# 3-VW_MODULE.net
KiCad netlist of a schematic drawn in Altium Designer
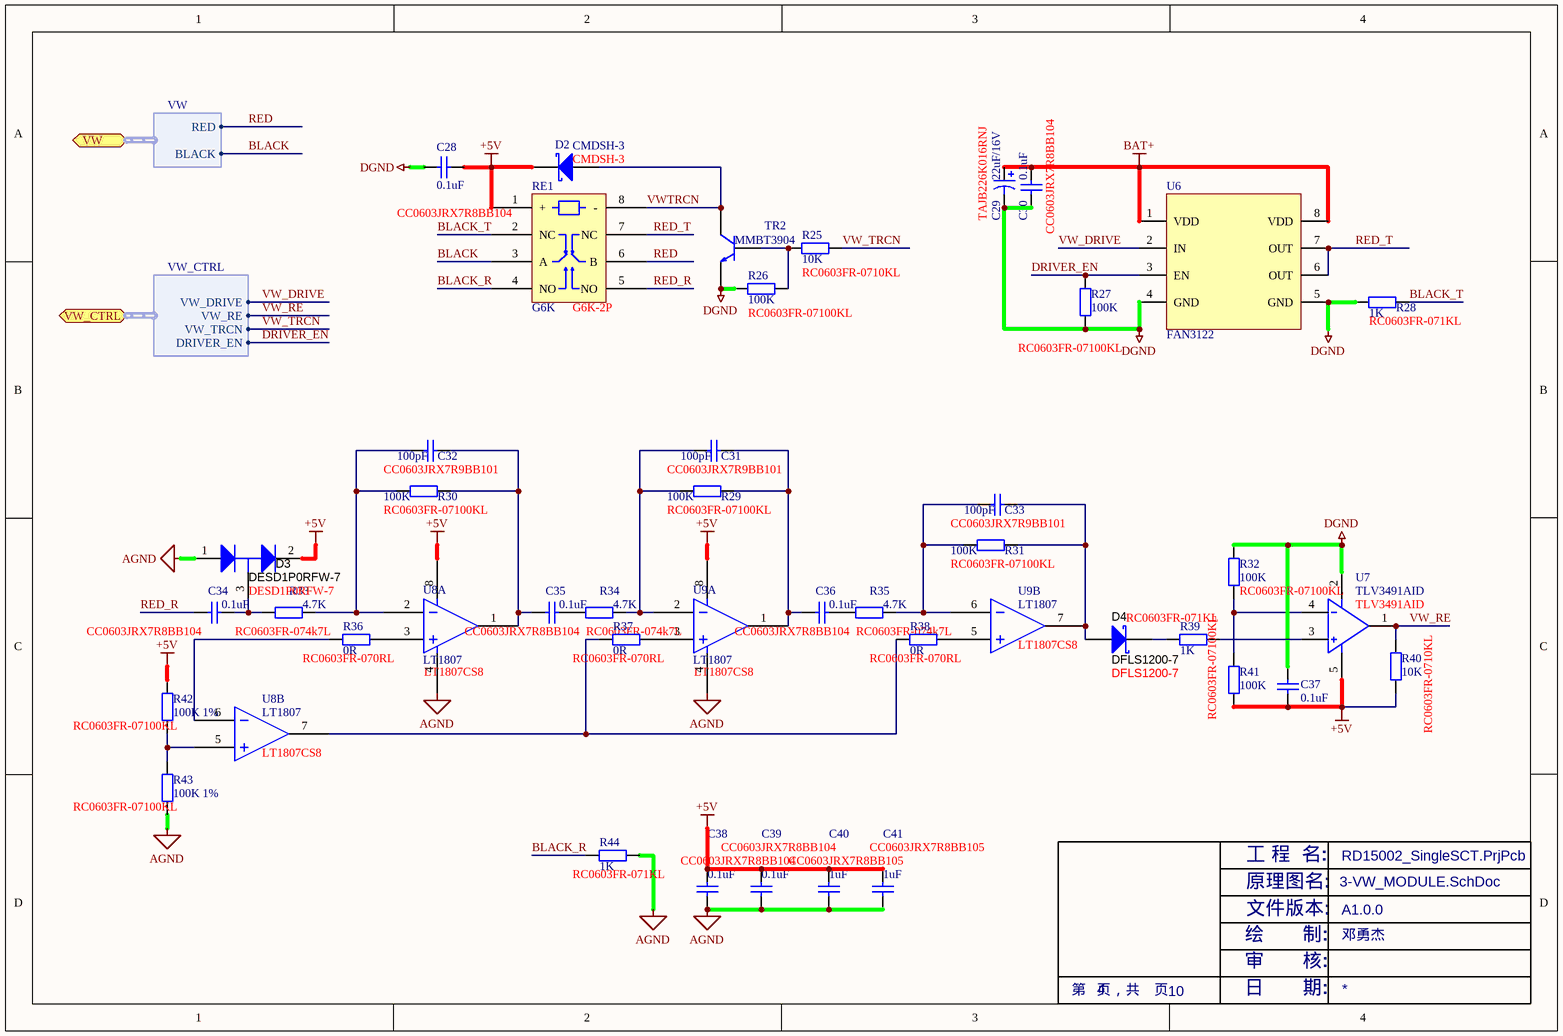
[diagram p0: 3-VW_MODULE.SchDoc]

(export (version "E")
  (design (tool "Eeschema 10.0.6"))
  (components
    (comp (ref "C28")
      (value "0.1uF")
      (footprint "CC0603")
      (description "Capacitor")
      (fields (field (name "TYPE NO.") "CC0603JRX7R8BB104"))
      (libsource (lib "Miscellaneous Devices") (part "Cap"))
    )
    (comp (ref "C29")
      (value "22uF/16V")
      (footprint "CB3528")
      (description "Polarized Capacitor (Radial)")
      (fields (field (name "PART NO.") "TAJB226K016RNJ"))
      (libsource (lib "Miscellaneous Devices") (part "Cap Pol1"))
    )
    (comp (ref "C30")
      (value "0.1uF")
      (footprint "CC0603")
      (description "Capacitor")
      (fields (field (name "TYPE NO.") "CC0603JRX7R8BB104"))
      (libsource (lib "Miscellaneous Devices") (part "Cap"))
    )
    (comp (ref "C31")
      (value "100pF")
      (footprint "CC0603")
      (description "Capacitor")
      (fields (field (name "TYPE NO.") "CC0603JRX7R9BB101"))
      (libsource (lib "Miscellaneous Devices") (part "Cap"))
    )
    (comp (ref "C32")
      (value "100pF")
      (footprint "CC0603")
      (description "Capacitor")
      (fields (field (name "TYPE NO.") "CC0603JRX7R9BB101"))
      (libsource (lib "Miscellaneous Devices") (part "Cap"))
    )
    (comp (ref "C33")
      (value "100pF")
      (footprint "CC0603")
      (description "Capacitor")
      (fields (field (name "TYPE NO.") "CC0603JRX7R9BB101"))
      (libsource (lib "Miscellaneous Devices") (part "Cap"))
    )
    (comp (ref "C34")
      (value "0.1uF")
      (footprint "CC0603")
      (description "Capacitor")
      (fields (field (name "TYPE NO.") "CC0603JRX7R8BB104"))
      (libsource (lib "Miscellaneous Devices") (part "Cap"))
    )
    (comp (ref "C35")
      (value "0.1uF")
      (footprint "CC0603")
      (description "Capacitor")
      (fields (field (name "TYPE NO.") "CC0603JRX7R8BB104"))
      (libsource (lib "Miscellaneous Devices") (part "Cap"))
    )
    (comp (ref "C36")
      (value "0.1uF")
      (footprint "CC0603")
      (description "Capacitor")
      (fields (field (name "TYPE NO.") "CC0603JRX7R8BB104"))
      (libsource (lib "Miscellaneous Devices") (part "Cap"))
    )
    (comp (ref "C37")
      (value "0.1uF")
      (footprint "CC0603")
      (description "Capacitor")
      (fields (field (name "PUBLISHER") "Altium Limited"))
      (libsource (lib "Miscellaneous Devices") (part "Cap"))
    )
    (comp (ref "C38")
      (value "0.1uF")
      (footprint "CC0603")
      (description "Capacitor")
      (fields (field (name "TYPE NO.") "CC0603JRX7R8BB104"))
      (libsource (lib "Miscellaneous Devices") (part "Cap"))
    )
    (comp (ref "C39")
      (value "0.1uF")
      (footprint "CC0603")
      (description "Capacitor")
      (fields (field (name "TYPE NO.") "CC0603JRX7R8BB104"))
      (libsource (lib "Miscellaneous Devices") (part "Cap"))
    )
    (comp (ref "C40")
      (value "1uF")
      (footprint "CC0603")
      (description "Capacitor")
      (fields (field (name "TYPE NO.") "CC0603JRX7R8BB105"))
      (libsource (lib "Miscellaneous Devices") (part "Cap"))
    )
    (comp (ref "C41")
      (value "1uF")
      (footprint "CC0603")
      (description "Capacitor")
      (fields (field (name "TYPE NO.") "CC0603JRX7R8BB105"))
      (libsource (lib "Miscellaneous Devices") (part "Cap"))
    )
    (comp (ref "D2")
      (value "CMDSH-3")
      (footprint "SOD323")
      (description "Schottky Diode")
      (fields (field (name "TYPE NO.") "CMDSH-3"))
      (libsource (lib "Miscellaneous Devices") (part "D Schottky"))
    )
    (comp (ref "D3")
      (value "DESD1P0RFW-7")
      (footprint "SOT-323")
      (description "TVS DIODE,70VVVM,8VC,SOT-323")
      (fields (field (name "TYPE NO.") "DESD1P0RFW-7"))
      (libsource (lib "Diode") (part "BAV99WT1G"))
    )
    (comp (ref "D4")
      (value "DFLS1200-7")
      (footprint "powerDI123")
      (description "Diode, Schotky, 200V, 1A, PowerDI123")
      (fields (field (name "PART NO.") "DFLS1200-7"))
      (libsource (lib "Diode") (part "DFLS1200-7"))
    )
    (comp (ref "R25")
      (value "10K")
      (footprint "CC0603")
      (description "Resistor")
      (fields (field (name "TYPE NO.") "RC0603FR-0710KL"))
      (libsource (lib "") (part "Res2_1"))
    )
    (comp (ref "R26")
      (value "100K")
      (footprint "CC0603")
      (description "Resistor")
      (fields (field (name "TYPE NO.") "RC0603FR-07100KL"))
      (libsource (lib "") (part "Res2_1"))
    )
    (comp (ref "R27")
      (value "100K")
      (footprint "CC0603")
      (description "Resistor")
      (fields (field (name "TYPE NO.") "RC0603FR-07100KL"))
      (libsource (lib "") (part "Res2_2"))
    )
    (comp (ref "R28")
      (value "1K")
      (footprint "CC0603")
      (description "Resistor")
      (fields (field (name "TYPE NO.") "RC0603FR-071KL"))
      (libsource (lib "Miscellaneous Devices") (part "Res2"))
    )
    (comp (ref "R29")
      (value "100K")
      (footprint "CC0603")
      (description "Resistor")
      (fields (field (name "TYPE NO.") "RC0603FR-07100KL"))
      (libsource (lib "Miscellaneous Devices") (part "Res2"))
    )
    (comp (ref "R30")
      (value "100K")
      (footprint "CC0603")
      (description "Resistor")
      (fields (field (name "TYPE NO.") "RC0603FR-07100KL"))
      (libsource (lib "Miscellaneous Devices") (part "Res2"))
    )
    (comp (ref "R31")
      (value "100K")
      (footprint "CC0603")
      (description "Resistor")
      (fields (field (name "TYPE NO.") "RC0603FR-07100KL"))
      (libsource (lib "Miscellaneous Devices") (part "Res2"))
    )
    (comp (ref "R32")
      (value "100K")
      (footprint "CC0603")
      (description "Resistor")
      (fields (field (name "TYPE NO.") "RC0603FR-07100KL"))
      (libsource (lib "") (part "Res2_1"))
    )
    (comp (ref "R33")
      (value "4.7K")
      (footprint "CC0603")
      (description "Resistor")
      (fields (field (name "TYPE NO.") "RC0603FR-074k7L"))
      (libsource (lib "Miscellaneous Devices") (part "Res2"))
    )
    (comp (ref "R34")
      (value "4.7K")
      (footprint "CC0603")
      (description "Resistor")
      (fields (field (name "TYPE NO.") "RC0603FR-074k7L"))
      (libsource (lib "Miscellaneous Devices") (part "Res2"))
    )
    (comp (ref "R35")
      (value "4.7K")
      (footprint "CC0603")
      (description "Resistor")
      (fields (field (name "TYPE NO.") "RC0603FR-074k7L"))
      (libsource (lib "Miscellaneous Devices") (part "Res2"))
    )
    (comp (ref "R36")
      (value "0R")
      (footprint "CC0603")
      (description "Resistor")
      (fields (field (name "TYPE NO.") "RC0603FR-070RL"))
      (libsource (lib "Miscellaneous Devices") (part "Res2"))
    )
    (comp (ref "R37")
      (value "0R")
      (footprint "CC0603")
      (description "Resistor")
      (fields (field (name "TYPE NO.") "RC0603FR-070RL"))
      (libsource (lib "Miscellaneous Devices") (part "Res2"))
    )
    (comp (ref "R38")
      (value "0R")
      (footprint "CC0603")
      (description "Resistor")
      (fields (field (name "TYPE NO.") "RC0603FR-070RL"))
      (libsource (lib "Miscellaneous Devices") (part "Res2"))
    )
    (comp (ref "R39")
      (value "1K")
      (footprint "CC0603")
      (description "Resistor")
      (fields (field (name "TYPE NO.") "RC0603FR-071KL"))
      (libsource (lib "Miscellaneous Devices") (part "Res2"))
    )
    (comp (ref "R40")
      (value "10K")
      (footprint "CC0603")
      (description "Resistor")
      (fields (field (name "TYPE NO.") "RC0603FR-0710KL"))
      (libsource (lib "") (part "Res2_1"))
    )
    (comp (ref "R41")
      (value "100K")
      (footprint "CC0603")
      (description "Resistor")
      (fields (field (name "TYPE NO.") "RC0603FR-07100KL"))
      (libsource (lib "") (part "Res2_1"))
    )
    (comp (ref "R42")
      (value "100K 1%")
      (footprint "CC0603")
      (description "Resistor")
      (fields (field (name "TYPE NO.") "RC0603FR-07100KL"))
      (libsource (lib "") (part "Res2_2"))
    )
    (comp (ref "R43")
      (value "100K 1%")
      (footprint "CC0603")
      (description "Resistor")
      (fields (field (name "TYPE NO.") "RC0603FR-07100KL"))
      (libsource (lib "") (part "Res2_2"))
    )
    (comp (ref "R44")
      (value "1K")
      (footprint "CC0603")
      (description "Resistor")
      (fields (field (name "TYPE NO.") "RC0603FR-071KL"))
      (libsource (lib "") (part "Res2_3"))
    )
    (comp (ref "RE1")
      (value "G6K")
      (footprint "G6K")
      (fields (field (name "TYPE NO.") "G6K-2P"))
      (libsource (lib "woylib2015") (part "G6K"))
    )
    (comp (ref "TR2") (value "MMBT3904") (footprint "SOT-23W") (libsource (lib "Discrete") (part "NPN")))
    (comp (ref "U6") (value "FAN3122") (footprint "SO-8") (libsource (lib "IC") (part "FAN3122")))
    (comp (ref "U7")
      (value "TLV3491AID")
      (footprint "SOT-23-5")
      (fields (field (name "TYPE NO.") "TLV3491AID"))
      (libsource (lib "woylib2015") (part "TLV3491AID"))
    )
    (comp (ref "U8")
      (value "LT1807")
      (footprint "SO-8")
      (fields (field (name "TYPE NO.") "LT1807CS8"))
      (libsource (lib "woylib2015") (part "LM833N"))
    )
    (comp (ref "U9")
      (value "LT1807")
      (footprint "SO-8")
      (fields (field (name "TYPE NO.") "LT1807CS8"))
      (libsource (lib "woylib2015") (part "LM833N"))
    )
  )
  (nets
    (net (code "3") (name "+5V") (class "Default")
      (node (ref "C28") (pin "1") (pinfunction "1_1") (pintype "passive"))
      (node (ref "C37") (pin "2") (pinfunction "2_2") (pintype "passive"))
      (node (ref "C38") (pin "2") (pinfunction "2_2") (pintype "passive"))
      (node (ref "C39") (pin "2") (pinfunction "2_2") (pintype "passive"))
      (node (ref "C40") (pin "2") (pinfunction "2_2") (pintype "passive"))
      (node (ref "C41") (pin "2") (pinfunction "2_2") (pintype "passive"))
      (node (ref "D2") (pin "2") (pinfunction "K_2") (pintype "passive"))
      (node (ref "D3") (pin "2") (pinfunction "K_2") (pintype "passive"))
      (node (ref "R40") (pin "1") (pinfunction "1_1") (pintype "passive"))
      (node (ref "R41") (pin "1") (pinfunction "1_1") (pintype "passive"))
      (node (ref "R42") (pin "1") (pinfunction "1_1") (pintype "passive"))
      (node (ref "RE1") (pin "1") (pinfunction "+_1") (pintype "passive"))
      (node (ref "U7") (pin "5") (pinfunction "+VS_5") (pintype "passive"))
      (node (ref "U8") (pin "8") (pintype "passive"))
      (node (ref "U9") (pin "8") (pintype "passive"))
    )
    (net (code "4") (name "/BLACK") (class "Default")
      (node (ref "RE1") (pin "3") (pinfunction "A_3") (pintype "passive"))
    )
    (net (code "5") (name "/BLACK_R") (class "Default")
      (node (ref "R44") (pin "1") (pinfunction "1_1") (pintype "passive"))
      (node (ref "RE1") (pin "4") (pinfunction "NO_4") (pintype "passive"))
    )
    (net (code "6") (name "/BLACK_T") (class "Default")
      (node (ref "R28") (pin "1") (pinfunction "1_1") (pintype "passive"))
      (node (ref "RE1") (pin "2") (pinfunction "NC_2") (pintype "passive"))
    )
    (net (code "7") (name "/DRIVER_EN") (class "Default")
      (node (ref "R27") (pin "1") (pinfunction "1_1") (pintype "passive"))
      (node (ref "U6") (pin "3") (pinfunction "EN_3") (pintype "passive"))
    )
    (net (code "8") (name "/RED") (class "Default")
      (node (ref "RE1") (pin "6") (pinfunction "B_6") (pintype "passive"))
    )
    (net (code "9") (name "/RED_R") (class "Default")
      (node (ref "C34") (pin "2") (pinfunction "2_2") (pintype "passive"))
      (node (ref "RE1") (pin "5") (pinfunction "NO_5") (pintype "passive"))
    )
    (net (code "10") (name "/RED_T") (class "Default")
      (node (ref "RE1") (pin "7") (pinfunction "NC_7") (pintype "passive"))
      (node (ref "U6") (pin "6") (pinfunction "OUT_6") (pintype "passive"))
      (node (ref "U6") (pin "7") (pinfunction "OUT_7") (pintype "passive"))
    )
    (net (code "11") (name "/VWTRCN") (class "Default")
      (node (ref "D2") (pin "1") (pinfunction "A_1") (pintype "passive"))
      (node (ref "RE1") (pin "8") (pinfunction "-_8") (pintype "passive"))
      (node (ref "TR2") (pin "3") (pinfunction "3_3") (pintype "passive"))
    )
    (net (code "12") (name "/VW_DRIVE") (class "Default")
      (node (ref "U6") (pin "2") (pinfunction "IN_2") (pintype "passive"))
    )
    (net (code "13") (name "/VW_RE") (class "Default")
      (node (ref "R40") (pin "2") (pinfunction "2_2") (pintype "passive"))
      (node (ref "U7") (pin "1") (pinfunction "OUT_1") (pintype "passive"))
    )
    (net (code "14") (name "/VW_TRCN") (class "Default")
      (node (ref "R25") (pin "2") (pinfunction "2_2") (pintype "passive"))
    )
    (net (code "17") (name "AGND") (class "Default")
      (node (ref "C38") (pin "1") (pinfunction "1_1") (pintype "passive"))
      (node (ref "C39") (pin "1") (pinfunction "1_1") (pintype "passive"))
      (node (ref "C40") (pin "1") (pinfunction "1_1") (pintype "passive"))
      (node (ref "C41") (pin "1") (pinfunction "1_1") (pintype "passive"))
      (node (ref "D3") (pin "1") (pinfunction "A_1") (pintype "passive"))
      (node (ref "R43") (pin "2") (pinfunction "2_2") (pintype "passive"))
      (node (ref "R44") (pin "2") (pinfunction "2_2") (pintype "passive"))
      (node (ref "U8") (pin "4") (pintype "passive"))
      (node (ref "U9") (pin "4") (pintype "passive"))
    )
    (net (code "18") (name "BAT+") (class "Default")
      (node (ref "C29") (pin "1") (pinfunction "1_1") (pintype "passive"))
      (node (ref "C30") (pin "2") (pinfunction "2_2") (pintype "passive"))
      (node (ref "U6") (pin "1") (pinfunction "VDD_1") (pintype "passive"))
      (node (ref "U6") (pin "8") (pinfunction "VDD_8") (pintype "passive"))
    )
    (net (code "19") (name "DGND") (class "Default")
      (node (ref "C28") (pin "2") (pinfunction "2_2") (pintype "passive"))
      (node (ref "C29") (pin "2") (pinfunction "2_2") (pintype "passive"))
      (node (ref "C30") (pin "1") (pinfunction "1_1") (pintype "passive"))
      (node (ref "C37") (pin "1") (pinfunction "1_1") (pintype "passive"))
      (node (ref "R26") (pin "1") (pinfunction "1_1") (pintype "passive"))
      (node (ref "R27") (pin "2") (pinfunction "2_2") (pintype "passive"))
      (node (ref "R28") (pin "2") (pinfunction "2_2") (pintype "passive"))
      (node (ref "R32") (pin "2") (pinfunction "2_2") (pintype "passive"))
      (node (ref "TR2") (pin "2") (pinfunction "2_2") (pintype "passive"))
      (node (ref "U6") (pin "4") (pinfunction "GND_4") (pintype "passive"))
      (node (ref "U6") (pin "5") (pinfunction "GND_5") (pintype "passive"))
      (node (ref "U7") (pin "2") (pinfunction "-VS_2") (pintype "passive"))
    )
    (net (code "20") (name "Net-(C31-Pad1)") (class "Default")
      (node (ref "C31") (pin "1") (pinfunction "1_1") (pintype "passive"))
      (node (ref "C36") (pin "2") (pinfunction "2_2") (pintype "passive"))
      (node (ref "R29") (pin "1") (pinfunction "1_1") (pintype "passive"))
      (node (ref "U9") (pin "1") (pintype "passive"))
    )
    (net (code "21") (name "Net-(C31-Pad2)") (class "Default")
      (node (ref "C31") (pin "2") (pinfunction "2_2") (pintype "passive"))
      (node (ref "R29") (pin "2") (pinfunction "2_2") (pintype "passive"))
      (node (ref "R34") (pin "1") (pinfunction "1_1") (pintype "passive"))
      (node (ref "U9") (pin "2") (pintype "passive"))
    )
    (net (code "22") (name "Net-(C32-Pad1)") (class "Default")
      (node (ref "C32") (pin "1") (pinfunction "1_1") (pintype "passive"))
      (node (ref "C35") (pin "2") (pinfunction "2_2") (pintype "passive"))
      (node (ref "R30") (pin "1") (pinfunction "1_1") (pintype "passive"))
      (node (ref "U8") (pin "1") (pintype "passive"))
    )
    (net (code "23") (name "Net-(C32-Pad2)") (class "Default")
      (node (ref "C32") (pin "2") (pinfunction "2_2") (pintype "passive"))
      (node (ref "R30") (pin "2") (pinfunction "2_2") (pintype "passive"))
      (node (ref "R33") (pin "1") (pinfunction "1_1") (pintype "passive"))
      (node (ref "U8") (pin "2") (pintype "passive"))
    )
    (net (code "24") (name "Net-(C33-Pad2)") (class "Default")
      (node (ref "C33") (pin "2") (pinfunction "2_2") (pintype "passive"))
      (node (ref "R31") (pin "2") (pinfunction "2_2") (pintype "passive"))
      (node (ref "R35") (pin "1") (pinfunction "1_1") (pintype "passive"))
      (node (ref "U9") (pin "6") (pintype "passive"))
    )
    (net (code "25") (name "Net-(C35-Pad1)") (class "Default")
      (node (ref "C35") (pin "1") (pinfunction "1_1") (pintype "passive"))
      (node (ref "R34") (pin "2") (pinfunction "2_2") (pintype "passive"))
    )
    (net (code "26") (name "Net-(C36-Pad1)") (class "Default")
      (node (ref "C36") (pin "1") (pinfunction "1_1") (pintype "passive"))
      (node (ref "R35") (pin "2") (pinfunction "2_2") (pintype "passive"))
    )
    (net (code "27") (name "Net-(D3-C)") (class "Default")
      (node (ref "C34") (pin "1") (pinfunction "1_1") (pintype "passive"))
      (node (ref "D3") (pin "3") (pinfunction "C_3") (pintype "passive"))
      (node (ref "R33") (pin "2") (pinfunction "2_2") (pintype "passive"))
    )
    (net (code "28") (name "Net-(D4-A)") (class "Default")
      (node (ref "C33") (pin "1") (pinfunction "1_1") (pintype "passive"))
      (node (ref "D4") (pin "2") (pinfunction "A_2") (pintype "passive"))
      (node (ref "R31") (pin "1") (pinfunction "1_1") (pintype "passive"))
      (node (ref "U9") (pin "7") (pintype "passive"))
    )
    (net (code "29") (name "Net-(D4-K)") (class "Default")
      (node (ref "D4") (pin "1") (pinfunction "K_1") (pintype "passive"))
      (node (ref "R39") (pin "2") (pinfunction "2_2") (pintype "passive"))
    )
    (net (code "30") (name "Net-(R25-Pad1)") (class "Default")
      (node (ref "R25") (pin "1") (pinfunction "1_1") (pintype "passive"))
      (node (ref "R26") (pin "2") (pinfunction "2_2") (pintype "passive"))
      (node (ref "TR2") (pin "1") (pinfunction "1_1") (pintype "passive"))
    )
    (net (code "31") (name "Net-(R36-Pad1)") (class "Default")
      (node (ref "R36") (pin "1") (pinfunction "1_1") (pintype "passive"))
      (node (ref "U8") (pin "3") (pintype "passive"))
    )
    (net (code "32") (name "Net-(R36-Pad2)") (class "Default")
      (node (ref "R36") (pin "2") (pinfunction "2_2") (pintype "passive"))
      (node (ref "U8") (pin "6") (pintype "passive"))
    )
    (net (code "33") (name "Net-(R37-Pad1)") (class "Default")
      (node (ref "R37") (pin "1") (pinfunction "1_1") (pintype "passive"))
      (node (ref "U9") (pin "3") (pintype "passive"))
    )
    (net (code "34") (name "Net-(R37-Pad2)") (class "Default")
      (node (ref "R37") (pin "2") (pinfunction "2_2") (pintype "passive"))
      (node (ref "R38") (pin "2") (pinfunction "2_2") (pintype "passive"))
      (node (ref "U8") (pin "7") (pintype "passive"))
    )
    (net (code "35") (name "Net-(R38-Pad1)") (class "Default")
      (node (ref "R38") (pin "1") (pinfunction "1_1") (pintype "passive"))
      (node (ref "U9") (pin "5") (pintype "passive"))
    )
    (net (code "36") (name "Net-(R42-Pad2)") (class "Default")
      (node (ref "R42") (pin "2") (pinfunction "2_2") (pintype "passive"))
      (node (ref "R43") (pin "1") (pinfunction "1_1") (pintype "passive"))
      (node (ref "U8") (pin "5") (pintype "passive"))
    )
    (net (code "37") (name "Net-(U7-+)") (class "Default")
      (node (ref "R39") (pin "1") (pinfunction "1_1") (pintype "passive"))
      (node (ref "U7") (pin "3") (pinfunction "+_3") (pintype "passive"))
    )
    (net (code "38") (name "Net-(U7--)") (class "Default")
      (node (ref "R32") (pin "1") (pinfunction "1_1") (pintype "passive"))
      (node (ref "R41") (pin "2") (pinfunction "2_2") (pintype "passive"))
      (node (ref "U7") (pin "4") (pinfunction "-_4") (pintype "passive"))
    )
  )
)
